# CustomHardwareSchematic.net
KiCad netlist of a schematic drawn in EAGLE
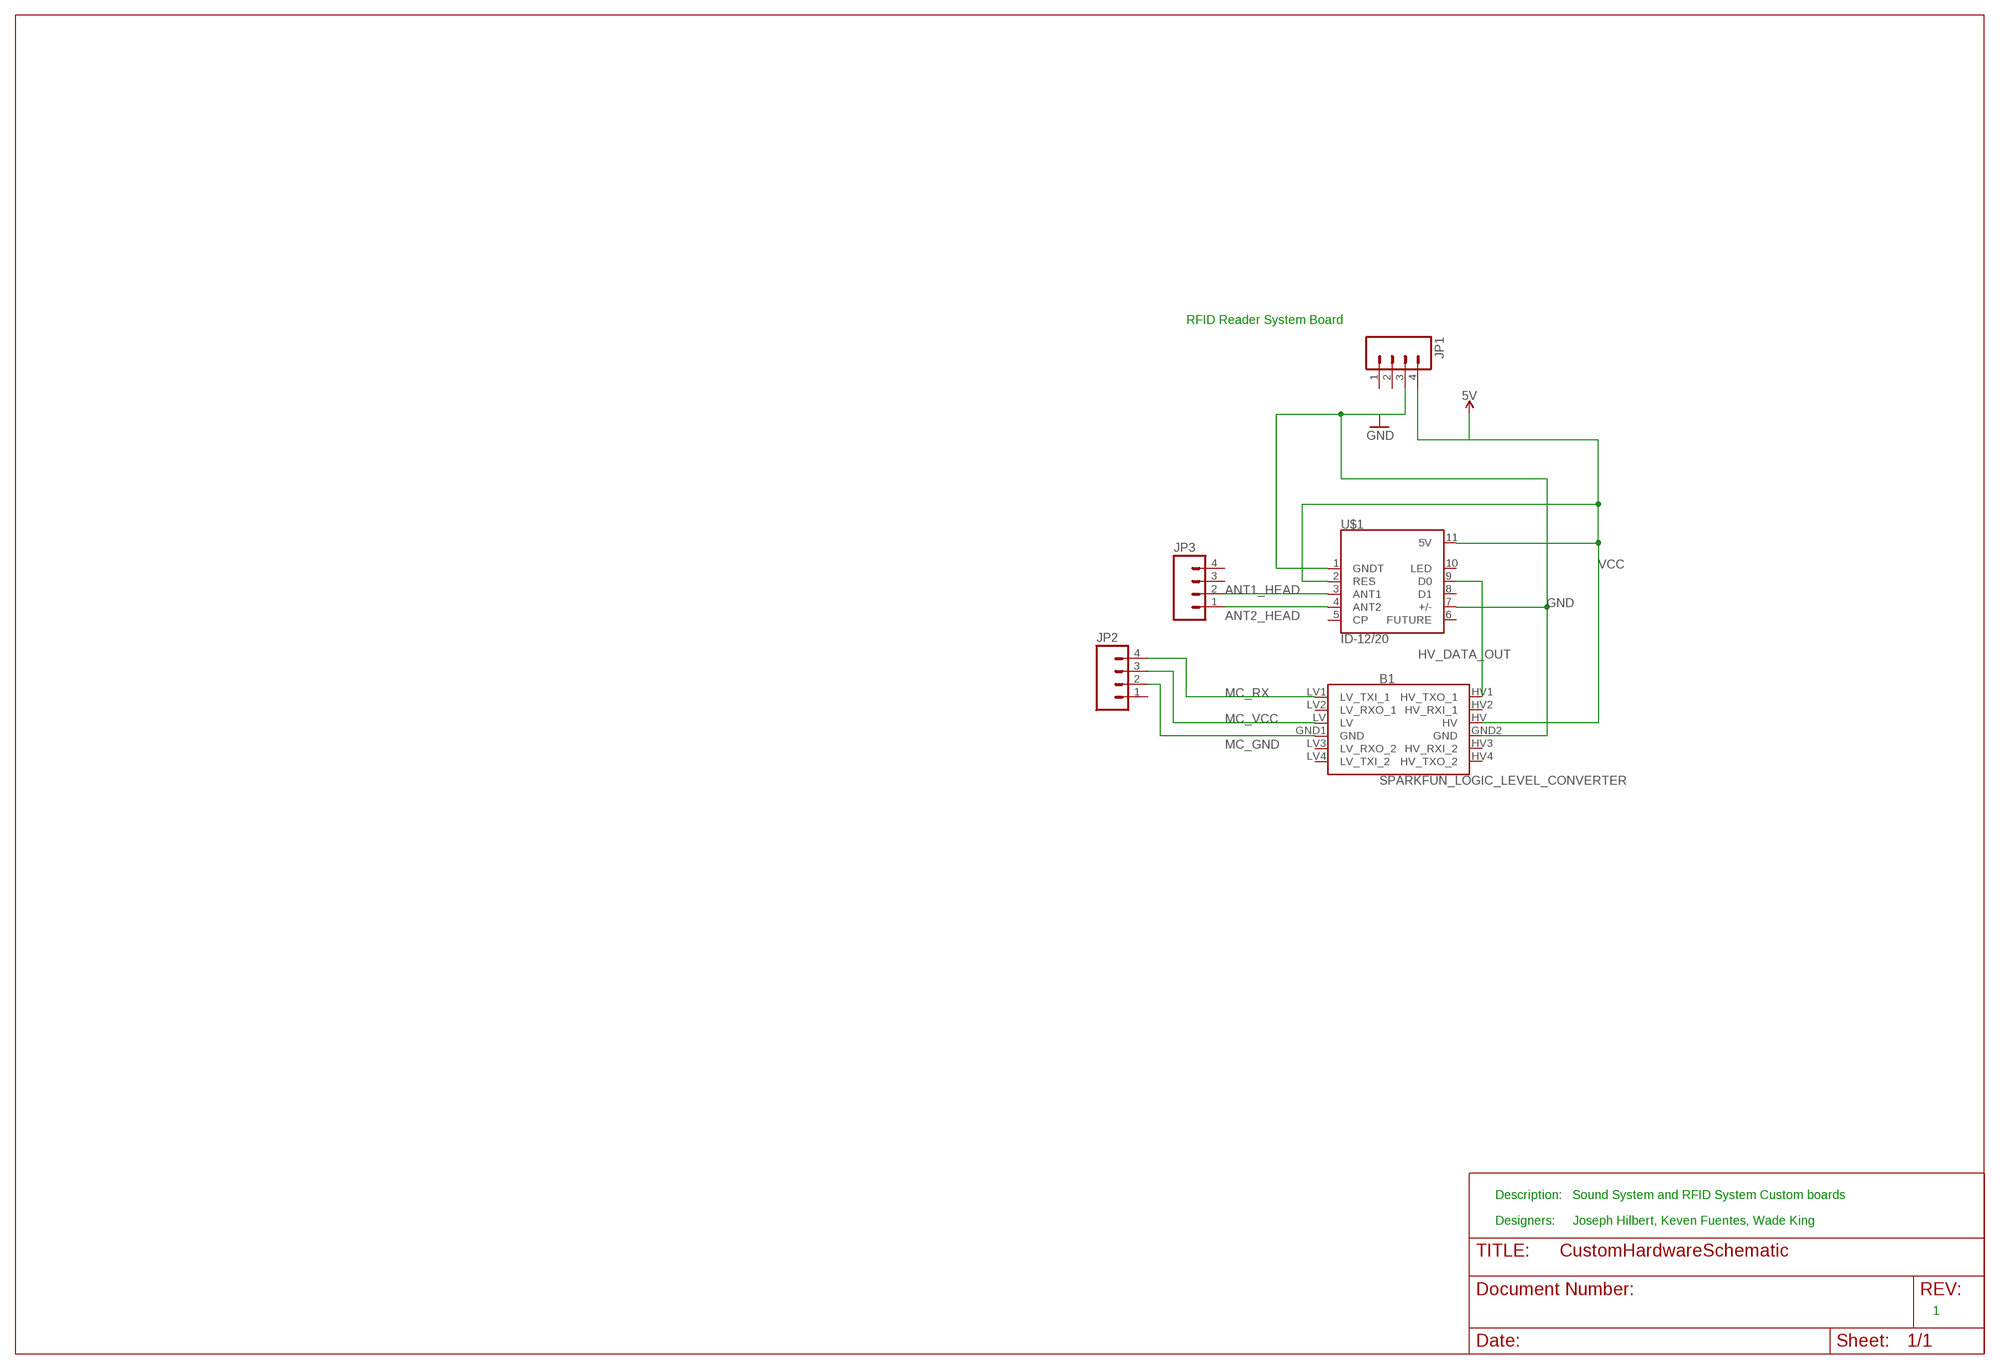
[diagram p0: schematic, sheet 1]

(export (version "E")
  (design (tool "Eeschema 10.0.6"))
  (components
    (comp (ref "B1")
      (value "SPARKFUN_LOGIC_LEVEL_CONVERTER")
      (footprint "eagle-import:SPARKFUN_LOGIC_LEVEL_CONVERTER")
      (libsource (lib "eagle-import") (part "SPARKFUN_LOGIC_LEVEL_CONVERTER"))
    )
    (comp (ref "JP1")
      (value "M04LOCK")
      (footprint "eagle-import:1X04_LOCK")
      (libsource (lib "eagle-import") (part "M04LOCK"))
    )
    (comp (ref "JP2")
      (value "M04LOCK")
      (footprint "eagle-import:1X04_LOCK")
      (libsource (lib "eagle-import") (part "M04LOCK"))
    )
    (comp (ref "JP3")
      (value "M04LOCK")
      (footprint "eagle-import:1X04_LOCK")
      (libsource (lib "eagle-import") (part "M04LOCK"))
    )
    (comp (ref "U$1")
      (value "ID-12/20")
      (footprint "eagle-import:ID-12")
      (libsource (lib "eagle-import") (part "ID-12/20"))
    )
  )
  (nets
    (net (code "1") (name "/ANT1_HEAD") (class "Default")
      (node (ref "JP3") (pin "2") (pinfunction "2_2") (pintype "passive"))
      (node (ref "U$1") (pin "3") (pinfunction "ANT1_3") (pintype "bidirectional"))
    )
    (net (code "2") (name "/ANT2_HEAD") (class "Default")
      (node (ref "JP3") (pin "1") (pinfunction "1_1") (pintype "passive"))
      (node (ref "U$1") (pin "4") (pinfunction "ANT2_4") (pintype "bidirectional"))
    )
    (net (code "3") (name "/HV_DATA_OUT") (class "Default")
      (node (ref "B1") (pin "HV1") (pinfunction "HV_TXO_1_HV1") (pintype "bidirectional"))
      (node (ref "U$1") (pin "9") (pinfunction "D0_9") (pintype "bidirectional"))
    )
    (net (code "4") (name "/MC_GND") (class "Default")
      (node (ref "B1") (pin "GND1") (pinfunction "GND_GND1") (pintype "power_in"))
      (node (ref "JP2") (pin "2") (pinfunction "2_2") (pintype "passive"))
    )
    (net (code "5") (name "/MC_RX") (class "Default")
      (node (ref "B1") (pin "LV1") (pinfunction "LV_TXI_1_LV1") (pintype "bidirectional"))
      (node (ref "JP2") (pin "4") (pinfunction "4_4") (pintype "passive"))
    )
    (net (code "6") (name "/MC_VCC") (class "Default")
      (node (ref "B1") (pin "LV") (pinfunction "LV_LV") (pintype "power_in"))
      (node (ref "JP2") (pin "3") (pinfunction "3_3") (pintype "passive"))
    )
    (net (code "7") (name "5V") (class "Default")
      (node (ref "B1") (pin "HV") (pinfunction "HV_HV") (pintype "power_in"))
      (node (ref "JP1") (pin "4") (pinfunction "4_4") (pintype "passive"))
      (node (ref "U$1") (pin "11") (pinfunction "5V_11") (pintype "bidirectional"))
      (node (ref "U$1") (pin "2") (pinfunction "RES_2") (pintype "bidirectional"))
    )
    (net (code "8") (name "GND") (class "Default")
      (node (ref "B1") (pin "GND2") (pinfunction "GND_GND2") (pintype "power_in"))
      (node (ref "JP1") (pin "3") (pinfunction "3_3") (pintype "passive"))
      (node (ref "U$1") (pin "1") (pinfunction "GNDT_1") (pintype "bidirectional"))
      (node (ref "U$1") (pin "7") (pinfunction "+/-_7") (pintype "bidirectional"))
    )
    (net (code "9") (name "unconnected-(B1-HV_RXI_1-PadHV2)") (class "Default")
      (node (ref "B1") (pin "HV2") (pinfunction "HV_RXI_1_HV2") (pintype "bidirectional"))
    )
    (net (code "10") (name "unconnected-(B1-HV_RXI_2-PadHV3)") (class "Default")
      (node (ref "B1") (pin "HV3") (pinfunction "HV_RXI_2_HV3") (pintype "bidirectional"))
    )
    (net (code "11") (name "unconnected-(B1-HV_TXO_2-PadHV4)") (class "Default")
      (node (ref "B1") (pin "HV4") (pinfunction "HV_TXO_2_HV4") (pintype "bidirectional"))
    )
    (net (code "12") (name "unconnected-(B1-LV_RXO_1-PadLV2)") (class "Default")
      (node (ref "B1") (pin "LV2") (pinfunction "LV_RXO_1_LV2") (pintype "bidirectional"))
    )
    (net (code "13") (name "unconnected-(B1-LV_RXO_2-PadLV3)") (class "Default")
      (node (ref "B1") (pin "LV3") (pinfunction "LV_RXO_2_LV3") (pintype "bidirectional"))
    )
    (net (code "14") (name "unconnected-(B1-LV_TXI_2-PadLV4)") (class "Default")
      (node (ref "B1") (pin "LV4") (pinfunction "LV_TXI_2_LV4") (pintype "bidirectional"))
    )
    (net (code "15") (name "unconnected-(JP1-Pad1)") (class "Default")
      (node (ref "JP1") (pin "1") (pinfunction "1_1") (pintype "passive"))
    )
    (net (code "16") (name "unconnected-(JP1-Pad2)") (class "Default")
      (node (ref "JP1") (pin "2") (pinfunction "2_2") (pintype "passive"))
    )
    (net (code "17") (name "unconnected-(JP2-Pad1)") (class "Default")
      (node (ref "JP2") (pin "1") (pinfunction "1_1") (pintype "passive"))
    )
    (net (code "18") (name "unconnected-(JP3-Pad3)") (class "Default")
      (node (ref "JP3") (pin "3") (pinfunction "3_3") (pintype "passive"))
    )
    (net (code "19") (name "unconnected-(JP3-Pad4)") (class "Default")
      (node (ref "JP3") (pin "4") (pinfunction "4_4") (pintype "passive"))
    )
    (net (code "20") (name "unconnected-(U$1-CP-Pad5)") (class "Default")
      (node (ref "U$1") (pin "5") (pinfunction "CP_5") (pintype "bidirectional"))
    )
    (net (code "21") (name "unconnected-(U$1-D1-Pad8)") (class "Default")
      (node (ref "U$1") (pin "8") (pinfunction "D1_8") (pintype "bidirectional"))
    )
    (net (code "22") (name "unconnected-(U$1-FUTURE-Pad6)") (class "Default")
      (node (ref "U$1") (pin "6") (pinfunction "FUTURE_6") (pintype "bidirectional"))
    )
    (net (code "23") (name "unconnected-(U$1-LED-Pad10)") (class "Default")
      (node (ref "U$1") (pin "10") (pinfunction "LED_10") (pintype "bidirectional"))
    )
  )
)
